# CompleteEdition1.net
KiCad netlist of a schematic drawn in EAGLE
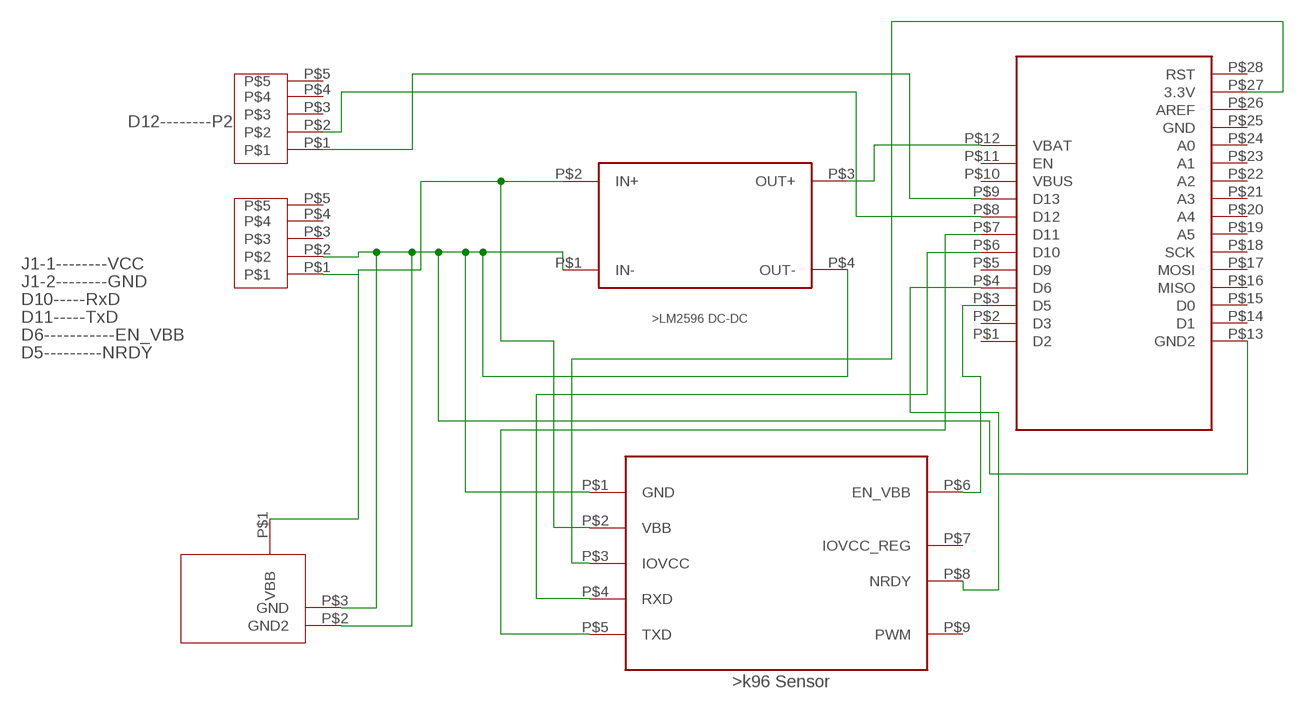
[diagram p0: schematic, sheet 1]

(export (version "E")
  (design (tool "Eeschema 10.0.6"))
  (components
    (comp (ref "DCDC1")
      (value "DCDC")
      (footprint "eagle-import:DCDC")
      (libsource (lib "eagle-import") (part "DCDC"))
    )
    (comp (ref "FEATHER1")
      (value "FEATHER")
      (footprint "eagle-import:FEATHER")
      (libsource (lib "eagle-import") (part "FEATHER"))
    )
    (comp (ref "K96SENSOR1")
      (value "K96SENSOR")
      (footprint "eagle-import:K96SENSOR")
      (libsource (lib "eagle-import") (part "K96SENSOR"))
    )
    (comp (ref "PIN1")
      (value "PIN")
      (footprint "eagle-import:PIN")
      (libsource (lib "eagle-import") (part "PIN"))
    )
    (comp (ref "PIN2")
      (value "PIN")
      (footprint "eagle-import:PIN")
      (libsource (lib "eagle-import") (part "PIN"))
    )
    (comp (ref "U$1")
      (value "POWER")
      (footprint "eagle-import:POWERIN")
      (libsource (lib "eagle-import") (part "POWER"))
    )
  )
  (nets
    (net (code "1") (name "Net-(DCDC1-IN+)") (class "Default")
      (node (ref "DCDC1") (pin "P$2") (pinfunction "IN+_P$2") (pintype "bidirectional"))
      (node (ref "K96SENSOR1") (pin "P$2") (pinfunction "VBB_P$2") (pintype "bidirectional"))
      (node (ref "PIN1") (pin "P$1") (pinfunction "P$1_P$1") (pintype "bidirectional"))
      (node (ref "U$1") (pin "P$1") (pinfunction "VBB_P$1") (pintype "bidirectional"))
    )
    (net (code "2") (name "Net-(DCDC1-IN-)") (class "Default")
      (node (ref "DCDC1") (pin "P$1") (pinfunction "IN-_P$1") (pintype "bidirectional"))
      (node (ref "DCDC1") (pin "P$4") (pinfunction "OUT-_P$4") (pintype "bidirectional"))
      (node (ref "FEATHER1") (pin "P$13") (pinfunction "GND2_P$13") (pintype "bidirectional"))
      (node (ref "K96SENSOR1") (pin "P$1") (pinfunction "GND_P$1") (pintype "bidirectional"))
      (node (ref "PIN1") (pin "P$2") (pinfunction "P$2_P$2") (pintype "bidirectional"))
      (node (ref "U$1") (pin "P$2") (pinfunction "GND2_P$2") (pintype "bidirectional"))
      (node (ref "U$1") (pin "P$3") (pinfunction "GND_P$3") (pintype "bidirectional"))
    )
    (net (code "3") (name "Net-(DCDC1-OUT+)") (class "Default")
      (node (ref "DCDC1") (pin "P$3") (pinfunction "OUT+_P$3") (pintype "bidirectional"))
      (node (ref "FEATHER1") (pin "P$12") (pinfunction "VBAT_P$12") (pintype "bidirectional"))
    )
    (net (code "4") (name "Net-(FEATHER1-3.3V)") (class "Default")
      (node (ref "FEATHER1") (pin "P$27") (pinfunction "3.3V_P$27") (pintype "bidirectional"))
      (node (ref "K96SENSOR1") (pin "P$3") (pinfunction "IOVCC_P$3") (pintype "bidirectional"))
    )
    (net (code "5") (name "Net-(FEATHER1-D5)") (class "Default")
      (node (ref "FEATHER1") (pin "P$3") (pinfunction "D5_P$3") (pintype "bidirectional"))
      (node (ref "K96SENSOR1") (pin "P$6") (pinfunction "EN_VBB_P$6") (pintype "bidirectional"))
    )
    (net (code "6") (name "Net-(FEATHER1-D6)") (class "Default")
      (node (ref "FEATHER1") (pin "P$4") (pinfunction "D6_P$4") (pintype "bidirectional"))
      (node (ref "K96SENSOR1") (pin "P$8") (pinfunction "NRDY_P$8") (pintype "bidirectional"))
    )
    (net (code "7") (name "Net-(FEATHER1-D10)") (class "Default")
      (node (ref "FEATHER1") (pin "P$6") (pinfunction "D10_P$6") (pintype "bidirectional"))
      (node (ref "K96SENSOR1") (pin "P$4") (pinfunction "RXD_P$4") (pintype "bidirectional"))
    )
    (net (code "8") (name "Net-(FEATHER1-D11)") (class "Default")
      (node (ref "FEATHER1") (pin "P$7") (pinfunction "D11_P$7") (pintype "bidirectional"))
      (node (ref "K96SENSOR1") (pin "P$5") (pinfunction "TXD_P$5") (pintype "bidirectional"))
    )
    (net (code "9") (name "Net-(FEATHER1-D12)") (class "Default")
      (node (ref "FEATHER1") (pin "P$8") (pinfunction "D12_P$8") (pintype "bidirectional"))
      (node (ref "PIN2") (pin "P$2") (pinfunction "P$2_P$2") (pintype "bidirectional"))
    )
    (net (code "10") (name "Net-(FEATHER1-D13)") (class "Default")
      (node (ref "FEATHER1") (pin "P$9") (pinfunction "D13_P$9") (pintype "bidirectional"))
      (node (ref "PIN2") (pin "P$1") (pinfunction "P$1_P$1") (pintype "bidirectional"))
    )
    (net (code "11") (name "unconnected-(FEATHER1-A0-PadP$24)") (class "Default")
      (node (ref "FEATHER1") (pin "P$24") (pinfunction "A0_P$24") (pintype "bidirectional"))
    )
    (net (code "12") (name "unconnected-(FEATHER1-A1-PadP$23)") (class "Default")
      (node (ref "FEATHER1") (pin "P$23") (pinfunction "A1_P$23") (pintype "bidirectional"))
    )
    (net (code "13") (name "unconnected-(FEATHER1-A2-PadP$22)") (class "Default")
      (node (ref "FEATHER1") (pin "P$22") (pinfunction "A2_P$22") (pintype "bidirectional"))
    )
    (net (code "14") (name "unconnected-(FEATHER1-A3-PadP$21)") (class "Default")
      (node (ref "FEATHER1") (pin "P$21") (pinfunction "A3_P$21") (pintype "bidirectional"))
    )
    (net (code "15") (name "unconnected-(FEATHER1-A4-PadP$20)") (class "Default")
      (node (ref "FEATHER1") (pin "P$20") (pinfunction "A4_P$20") (pintype "bidirectional"))
    )
    (net (code "16") (name "unconnected-(FEATHER1-A5-PadP$19)") (class "Default")
      (node (ref "FEATHER1") (pin "P$19") (pinfunction "A5_P$19") (pintype "bidirectional"))
    )
    (net (code "17") (name "unconnected-(FEATHER1-AREF-PadP$26)") (class "Default")
      (node (ref "FEATHER1") (pin "P$26") (pinfunction "AREF_P$26") (pintype "bidirectional"))
    )
    (net (code "18") (name "unconnected-(FEATHER1-D0-PadP$15)") (class "Default")
      (node (ref "FEATHER1") (pin "P$15") (pinfunction "D0_P$15") (pintype "bidirectional"))
    )
    (net (code "19") (name "unconnected-(FEATHER1-D1-PadP$14)") (class "Default")
      (node (ref "FEATHER1") (pin "P$14") (pinfunction "D1_P$14") (pintype "bidirectional"))
    )
    (net (code "20") (name "unconnected-(FEATHER1-D2-PadP$1)") (class "Default")
      (node (ref "FEATHER1") (pin "P$1") (pinfunction "D2_P$1") (pintype "bidirectional"))
    )
    (net (code "21") (name "unconnected-(FEATHER1-D3-PadP$2)") (class "Default")
      (node (ref "FEATHER1") (pin "P$2") (pinfunction "D3_P$2") (pintype "bidirectional"))
    )
    (net (code "22") (name "unconnected-(FEATHER1-D9-PadP$5)") (class "Default")
      (node (ref "FEATHER1") (pin "P$5") (pinfunction "D9_P$5") (pintype "bidirectional"))
    )
    (net (code "23") (name "unconnected-(FEATHER1-EN-PadP$11)") (class "Default")
      (node (ref "FEATHER1") (pin "P$11") (pinfunction "EN_P$11") (pintype "bidirectional"))
    )
    (net (code "24") (name "unconnected-(FEATHER1-GND-PadP$25)") (class "Default")
      (node (ref "FEATHER1") (pin "P$25") (pinfunction "GND_P$25") (pintype "bidirectional"))
    )
    (net (code "25") (name "unconnected-(FEATHER1-MISO-PadP$16)") (class "Default")
      (node (ref "FEATHER1") (pin "P$16") (pinfunction "MISO_P$16") (pintype "bidirectional"))
    )
    (net (code "26") (name "unconnected-(FEATHER1-MOSI-PadP$17)") (class "Default")
      (node (ref "FEATHER1") (pin "P$17") (pinfunction "MOSI_P$17") (pintype "bidirectional"))
    )
    (net (code "27") (name "unconnected-(FEATHER1-RST-PadP$28)") (class "Default")
      (node (ref "FEATHER1") (pin "P$28") (pinfunction "RST_P$28") (pintype "bidirectional"))
    )
    (net (code "28") (name "unconnected-(FEATHER1-SCK-PadP$18)") (class "Default")
      (node (ref "FEATHER1") (pin "P$18") (pinfunction "SCK_P$18") (pintype "bidirectional"))
    )
    (net (code "29") (name "unconnected-(FEATHER1-VBUS-PadP$10)") (class "Default")
      (node (ref "FEATHER1") (pin "P$10") (pinfunction "VBUS_P$10") (pintype "bidirectional"))
    )
    (net (code "30") (name "unconnected-(K96SENSOR1-IOVCC_REG-PadP$7)") (class "Default")
      (node (ref "K96SENSOR1") (pin "P$7") (pinfunction "IOVCC_REG_P$7") (pintype "bidirectional"))
    )
    (net (code "31") (name "unconnected-(K96SENSOR1-PWM-PadP$9)") (class "Default")
      (node (ref "K96SENSOR1") (pin "P$9") (pinfunction "PWM_P$9") (pintype "bidirectional"))
    )
    (net (code "32") (name "unconnected-(PIN1-PadP$3)") (class "Default")
      (node (ref "PIN1") (pin "P$3") (pinfunction "P$3_P$3") (pintype "bidirectional"))
    )
    (net (code "33") (name "unconnected-(PIN1-PadP$4)") (class "Default")
      (node (ref "PIN1") (pin "P$4") (pinfunction "P$4_P$4") (pintype "bidirectional"))
    )
    (net (code "34") (name "unconnected-(PIN1-PadP$5)") (class "Default")
      (node (ref "PIN1") (pin "P$5") (pinfunction "P$5_P$5") (pintype "bidirectional"))
    )
    (net (code "35") (name "unconnected-(PIN2-PadP$3)") (class "Default")
      (node (ref "PIN2") (pin "P$3") (pinfunction "P$3_P$3") (pintype "bidirectional"))
    )
    (net (code "36") (name "unconnected-(PIN2-PadP$4)") (class "Default")
      (node (ref "PIN2") (pin "P$4") (pinfunction "P$4_P$4") (pintype "bidirectional"))
    )
    (net (code "37") (name "unconnected-(PIN2-PadP$5)") (class "Default")
      (node (ref "PIN2") (pin "P$5") (pinfunction "P$5_P$5") (pintype "bidirectional"))
    )
  )
)
